# UA.net
KiCad netlist of a schematic drawn in Altium Designer
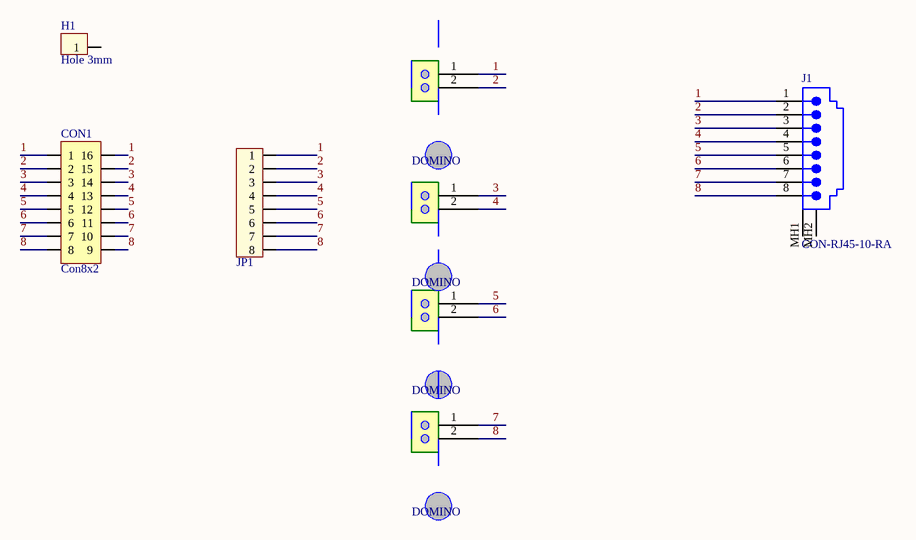
[diagram p0: UA.SchDoc]

(export (version "E")
  (design (tool "Eeschema 10.0.6"))
  (components
    (comp (ref "CON1") (value "Con8x2") (footprint "HEAD8x2") (libsource (lib "Thach") (part "Con8x2")))
    (comp (ref "D1") (value "DOMINO") (footprint "Domino2_small") (libsource (lib "Thach") (part "Domino 2")))
    (comp (ref "D2") (value "DOMINO") (footprint "Domino2_small") (libsource (lib "Thach") (part "Domino 2")))
    (comp (ref "D3") (value "DOMINO") (footprint "Domino2_small") (libsource (lib "Thach") (part "Domino 2")))
    (comp (ref "D4") (value "DOMINO") (footprint "Domino2_small") (libsource (lib "Thach") (part "Domino 2")))
    (comp (ref "H1") (value "Hole 3mm") (footprint "Hole_3mm") (libsource (lib "Thach") (part "Hole_3mm")))
    (comp (ref "J1")
      (value "CON-RJ45-10-RA")
      (footprint "RJ45_tme")
      (description "Right Angle, Standard Profile, External Shield PCB Jack")
      (libsource (lib "Thach") (part "CON-RJ45-10-RA"))
    )
    (comp (ref "JP1")
      (value "JP8")
      (footprint "CON8")
      (description "Connector 8")
      (libsource (lib "Thach") (part "Con8"))
    )
  )
  (nets
    (net (code "1") (name "/1") (class "Default")
      (node (ref "CON1") (pin "1") (pinfunction "1_1") (pintype "passive"))
      (node (ref "CON1") (pin "16") (pinfunction "16_16") (pintype "passive"))
      (node (ref "D1") (pin "1") (pintype "passive"))
      (node (ref "J1") (pin "1") (pinfunction "1_1") (pintype "passive"))
      (node (ref "JP1") (pin "1") (pinfunction "1_1") (pintype "passive"))
    )
    (net (code "2") (name "/2") (class "Default")
      (node (ref "CON1") (pin "15") (pinfunction "15_15") (pintype "passive"))
      (node (ref "CON1") (pin "2") (pinfunction "2_2") (pintype "passive"))
      (node (ref "D1") (pin "2") (pintype "passive"))
      (node (ref "J1") (pin "2") (pinfunction "2_2") (pintype "passive"))
      (node (ref "JP1") (pin "2") (pinfunction "2_2") (pintype "passive"))
    )
    (net (code "3") (name "/3") (class "Default")
      (node (ref "CON1") (pin "14") (pinfunction "14_14") (pintype "passive"))
      (node (ref "CON1") (pin "3") (pinfunction "3_3") (pintype "passive"))
      (node (ref "D2") (pin "1") (pintype "passive"))
      (node (ref "J1") (pin "3") (pinfunction "3_3") (pintype "passive"))
      (node (ref "JP1") (pin "3") (pinfunction "3_3") (pintype "passive"))
    )
    (net (code "4") (name "/4") (class "Default")
      (node (ref "CON1") (pin "13") (pinfunction "13_13") (pintype "passive"))
      (node (ref "CON1") (pin "4") (pinfunction "4_4") (pintype "passive"))
      (node (ref "D2") (pin "2") (pintype "passive"))
      (node (ref "J1") (pin "4") (pinfunction "4_4") (pintype "passive"))
      (node (ref "JP1") (pin "4") (pinfunction "4_4") (pintype "passive"))
    )
    (net (code "5") (name "/5") (class "Default")
      (node (ref "CON1") (pin "12") (pinfunction "12_12") (pintype "passive"))
      (node (ref "CON1") (pin "5") (pinfunction "5_5") (pintype "passive"))
      (node (ref "D3") (pin "1") (pintype "passive"))
      (node (ref "J1") (pin "5") (pinfunction "5_5") (pintype "passive"))
      (node (ref "JP1") (pin "5") (pinfunction "5_5") (pintype "passive"))
    )
    (net (code "6") (name "/6") (class "Default")
      (node (ref "CON1") (pin "11") (pinfunction "11_11") (pintype "passive"))
      (node (ref "CON1") (pin "6") (pinfunction "6_6") (pintype "passive"))
      (node (ref "D3") (pin "2") (pintype "passive"))
      (node (ref "J1") (pin "6") (pinfunction "6_6") (pintype "passive"))
      (node (ref "JP1") (pin "6") (pinfunction "6_6") (pintype "passive"))
    )
    (net (code "7") (name "/7") (class "Default")
      (node (ref "CON1") (pin "10") (pinfunction "10_10") (pintype "passive"))
      (node (ref "CON1") (pin "7") (pinfunction "7_7") (pintype "passive"))
      (node (ref "D4") (pin "1") (pintype "passive"))
      (node (ref "J1") (pin "7") (pinfunction "7_7") (pintype "passive"))
      (node (ref "JP1") (pin "7") (pinfunction "7_7") (pintype "passive"))
    )
    (net (code "8") (name "/8") (class "Default")
      (node (ref "CON1") (pin "8") (pinfunction "8_8") (pintype "passive"))
      (node (ref "CON1") (pin "9") (pinfunction "9_9") (pintype "passive"))
      (node (ref "D4") (pin "2") (pintype "passive"))
      (node (ref "J1") (pin "8") (pinfunction "8_8") (pintype "passive"))
      (node (ref "JP1") (pin "8") (pinfunction "8_8") (pintype "passive"))
    )
    (net (code "9") (name "unconnected-(H1-Pad1)") (class "Default")
      (node (ref "H1") (pin "1") (pinfunction "1_1") (pintype "passive"))
    )
    (net (code "10") (name "unconnected-(J1-Shield-PadMH1)") (class "Default")
      (node (ref "J1") (pin "MH1") (pinfunction "Shield_MH1") (pintype "passive"))
    )
    (net (code "11") (name "unconnected-(J1-Shield-PadMH2)") (class "Default")
      (node (ref "J1") (pin "MH2") (pinfunction "Shield_MH2") (pintype "passive"))
    )
  )
)
